# CC110L_Breakout.net
KiCad netlist of a schematic drawn in EAGLE
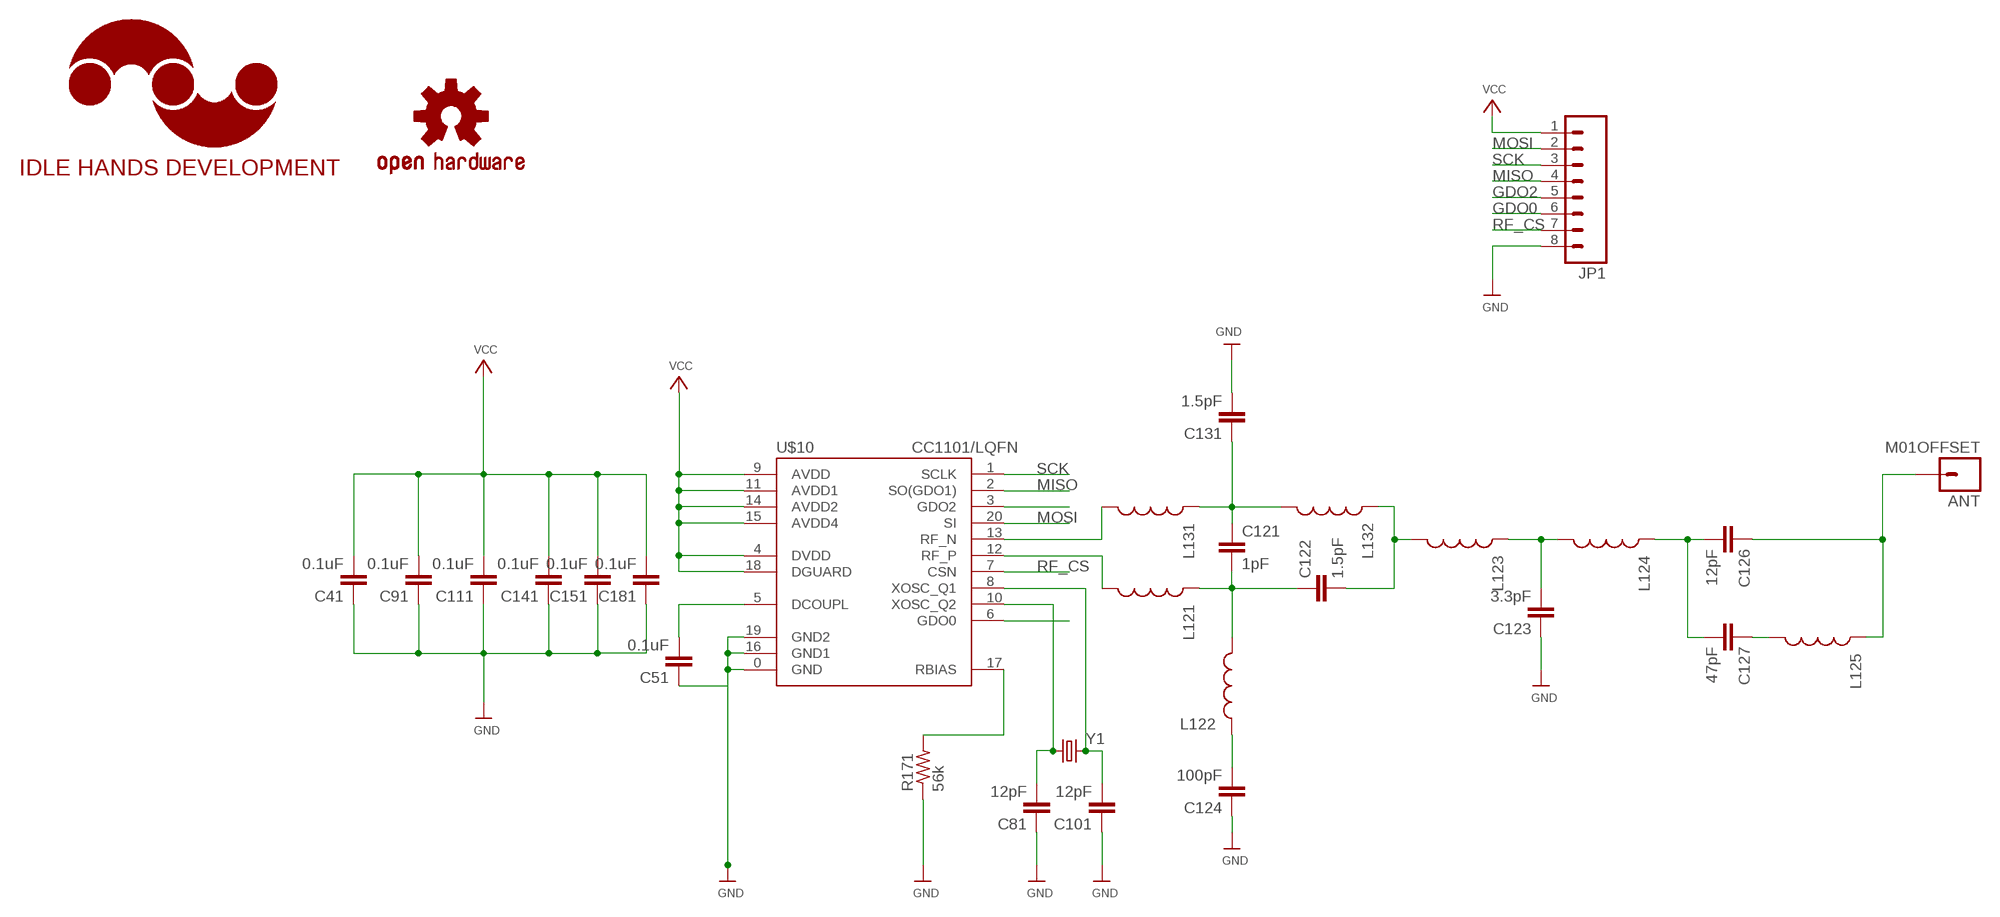
[diagram p0: schematic, sheet 1]

(export (version "E")
  (design (tool "Eeschema 10.0.6"))
  (components
    (comp (ref "ANT")
      (value "M01OFFSET")
      (footprint "eagle-import:1X01_OFFSET")
      (libsource (lib "eagle-import") (part "M01OFFSET"))
    )
    (comp (ref "C41")
      (value "0.1uF")
      (footprint "eagle-import:C0402")
      (libsource (lib "eagle-import") (part "C-EUC0402"))
    )
    (comp (ref "C51")
      (value "0.1uF")
      (footprint "eagle-import:C0402")
      (libsource (lib "eagle-import") (part "C-EUC0402"))
    )
    (comp (ref "C81")
      (value "12pF")
      (footprint "eagle-import:C0402")
      (libsource (lib "eagle-import") (part "C-EUC0402"))
    )
    (comp (ref "C91")
      (value "0.1uF")
      (footprint "eagle-import:C0402")
      (libsource (lib "eagle-import") (part "C-EUC0402"))
    )
    (comp (ref "C101")
      (value "12pF")
      (footprint "eagle-import:C0402")
      (libsource (lib "eagle-import") (part "C-EUC0402"))
    )
    (comp (ref "C111")
      (value "0.1uF")
      (footprint "eagle-import:C0402")
      (libsource (lib "eagle-import") (part "C-EUC0402"))
    )
    (comp (ref "C121")
      (value "1pF")
      (footprint "eagle-import:C0402")
      (libsource (lib "eagle-import") (part "C-EUC0402"))
    )
    (comp (ref "C122")
      (value "1.5pF")
      (footprint "eagle-import:C0402")
      (libsource (lib "eagle-import") (part "C-EUC0402"))
    )
    (comp (ref "C123")
      (value "3.3pF")
      (footprint "eagle-import:C0402")
      (libsource (lib "eagle-import") (part "C-EUC0402"))
    )
    (comp (ref "C124")
      (value "100pF")
      (footprint "eagle-import:C0402")
      (libsource (lib "eagle-import") (part "C-EUC0402"))
    )
    (comp (ref "C126")
      (value "12pF")
      (footprint "eagle-import:C0402")
      (libsource (lib "eagle-import") (part "C-EUC0402"))
    )
    (comp (ref "C127")
      (value "47pF")
      (footprint "eagle-import:C0402")
      (libsource (lib "eagle-import") (part "C-EUC0402"))
    )
    (comp (ref "C131")
      (value "1.5pF")
      (footprint "eagle-import:C0402")
      (libsource (lib "eagle-import") (part "C-EUC0402"))
    )
    (comp (ref "C141")
      (value "0.1uF")
      (footprint "eagle-import:C0402")
      (libsource (lib "eagle-import") (part "C-EUC0402"))
    )
    (comp (ref "C151")
      (value "0.1uF")
      (footprint "eagle-import:C0402")
      (libsource (lib "eagle-import") (part "C-EUC0402"))
    )
    (comp (ref "C181")
      (value "0.1uF")
      (footprint "eagle-import:C0402")
      (libsource (lib "eagle-import") (part "C-EUC0402"))
    )
    (comp (ref "JP1")
      (value "M08LOCK")
      (footprint "eagle-import:1X08_LOCK")
      (libsource (lib "eagle-import") (part "M08LOCK"))
    )
    (comp (ref "L121")
      (value "INDUCTOR0402")
      (footprint "eagle-import:C0402")
      (libsource (lib "eagle-import") (part "INDUCTOR0402"))
    )
    (comp (ref "L122")
      (value "INDUCTOR0402")
      (footprint "eagle-import:C0402")
      (libsource (lib "eagle-import") (part "INDUCTOR0402"))
    )
    (comp (ref "L123")
      (value "INDUCTOR0402")
      (footprint "eagle-import:C0402")
      (libsource (lib "eagle-import") (part "INDUCTOR0402"))
    )
    (comp (ref "L124")
      (value "INDUCTOR0402")
      (footprint "eagle-import:C0402")
      (libsource (lib "eagle-import") (part "INDUCTOR0402"))
    )
    (comp (ref "L125")
      (value "INDUCTOR0402")
      (footprint "eagle-import:C0402")
      (libsource (lib "eagle-import") (part "INDUCTOR0402"))
    )
    (comp (ref "L131")
      (value "INDUCTOR0402")
      (footprint "eagle-import:C0402")
      (libsource (lib "eagle-import") (part "INDUCTOR0402"))
    )
    (comp (ref "L132")
      (value "INDUCTOR0402")
      (footprint "eagle-import:C0402")
      (libsource (lib "eagle-import") (part "INDUCTOR0402"))
    )
    (comp (ref "LOGO1")
      (value "OSHW-LOGOS")
      (footprint "eagle-import:OSHW-LOGO-S")
      (libsource (lib "eagle-import") (part "OSHW-LOGOS"))
    )
    (comp (ref "LOGO2")
      (value "IDLEHANDS_LOGOS")
      (footprint "eagle-import:IHD-LOGO-S")
      (libsource (lib "eagle-import") (part "IDLEHANDS_LOGOS"))
    )
    (comp (ref "R171")
      (value "56k")
      (footprint "eagle-import:R0402")
      (libsource (lib "eagle-import") (part "R-US_R0402"))
    )
    (comp (ref "U$10")
      (value "CC1101/LQFN")
      (footprint "eagle-import:QFN20")
      (libsource (lib "eagle-import") (part "CC1101/LQFN"))
    )
    (comp (ref "Y1")
      (value "CRYSTAL3.2X2.5")
      (footprint "eagle-import:CRYSTAL-SMD-3.2X2.5")
      (libsource (lib "eagle-import") (part "CRYSTAL3.2X2.5"))
    )
  )
  (nets
    (net (code "1") (name "/GDO0") (class "Default")
      (node (ref "JP1") (pin "6") (pinfunction "6_6") (pintype "passive"))
      (node (ref "U$10") (pin "6") (pinfunction "GDO0_6") (pintype "bidirectional"))
    )
    (net (code "2") (name "/GDO2") (class "Default")
      (node (ref "JP1") (pin "5") (pinfunction "5_5") (pintype "passive"))
      (node (ref "U$10") (pin "3") (pinfunction "GDO2_3") (pintype "bidirectional"))
    )
    (net (code "3") (name "/MISO") (class "Default")
      (node (ref "JP1") (pin "4") (pinfunction "4_4") (pintype "passive"))
      (node (ref "U$10") (pin "2") (pinfunction "SO(GDO1)_2") (pintype "bidirectional"))
    )
    (net (code "4") (name "/MOSI") (class "Default")
      (node (ref "JP1") (pin "2") (pinfunction "2_2") (pintype "passive"))
      (node (ref "U$10") (pin "20") (pinfunction "SI_20") (pintype "bidirectional"))
    )
    (net (code "5") (name "/RF_CS") (class "Default")
      (node (ref "JP1") (pin "7") (pinfunction "7_7") (pintype "passive"))
      (node (ref "U$10") (pin "7") (pinfunction "CSN_7") (pintype "bidirectional"))
    )
    (net (code "6") (name "/SCK") (class "Default")
      (node (ref "JP1") (pin "3") (pinfunction "3_3") (pintype "passive"))
      (node (ref "U$10") (pin "1") (pinfunction "SCLK_1") (pintype "bidirectional"))
    )
    (net (code "7") (name "GND") (class "Default")
      (node (ref "C101") (pin "1") (pinfunction "1_1") (pintype "passive"))
      (node (ref "C111") (pin "1") (pinfunction "1_1") (pintype "passive"))
      (node (ref "C123") (pin "1") (pinfunction "1_1") (pintype "passive"))
      (node (ref "C124") (pin "1") (pinfunction "1_1") (pintype "passive"))
      (node (ref "C131") (pin "2") (pinfunction "2_2") (pintype "passive"))
      (node (ref "C141") (pin "1") (pinfunction "1_1") (pintype "passive"))
      (node (ref "C151") (pin "1") (pinfunction "1_1") (pintype "passive"))
      (node (ref "C181") (pin "1") (pinfunction "1_1") (pintype "passive"))
      (node (ref "C41") (pin "1") (pinfunction "1_1") (pintype "passive"))
      (node (ref "C51") (pin "1") (pinfunction "1_1") (pintype "passive"))
      (node (ref "C81") (pin "1") (pinfunction "1_1") (pintype "passive"))
      (node (ref "C91") (pin "1") (pinfunction "1_1") (pintype "passive"))
      (node (ref "JP1") (pin "8") (pinfunction "8_8") (pintype "passive"))
      (node (ref "R171") (pin "1") (pinfunction "1_1") (pintype "passive"))
      (node (ref "U$10") (pin "0") (pinfunction "GND_0") (pintype "bidirectional"))
      (node (ref "U$10") (pin "16") (pinfunction "GND1_16") (pintype "bidirectional"))
      (node (ref "U$10") (pin "19") (pinfunction "GND2_19") (pintype "bidirectional"))
    )
    (net (code "8") (name "Net-(ANT-Pad1)") (class "Default")
      (node (ref "ANT") (pin "1") (pinfunction "1_1") (pintype "passive"))
      (node (ref "C126") (pin "1") (pinfunction "1_1") (pintype "passive"))
      (node (ref "L125") (pin "1") (pinfunction "1_1") (pintype "passive"))
    )
    (net (code "9") (name "Net-(C121-Pad1)") (class "Default")
      (node (ref "C121") (pin "1") (pinfunction "1_1") (pintype "passive"))
      (node (ref "C131") (pin "1") (pinfunction "1_1") (pintype "passive"))
      (node (ref "L131") (pin "1") (pinfunction "1_1") (pintype "passive"))
      (node (ref "L132") (pin "2") (pinfunction "2_2") (pintype "passive"))
    )
    (net (code "10") (name "Net-(C121-Pad2)") (class "Default")
      (node (ref "C121") (pin "2") (pinfunction "2_2") (pintype "passive"))
      (node (ref "C122") (pin "1") (pinfunction "1_1") (pintype "passive"))
      (node (ref "L121") (pin "1") (pinfunction "1_1") (pintype "passive"))
      (node (ref "L122") (pin "2") (pinfunction "2_2") (pintype "passive"))
    )
    (net (code "11") (name "Net-(C122-Pad2)") (class "Default")
      (node (ref "C122") (pin "2") (pinfunction "2_2") (pintype "passive"))
      (node (ref "L123") (pin "2") (pinfunction "2_2") (pintype "passive"))
      (node (ref "L132") (pin "1") (pinfunction "1_1") (pintype "passive"))
    )
    (net (code "12") (name "Net-(C123-Pad2)") (class "Default")
      (node (ref "C123") (pin "2") (pinfunction "2_2") (pintype "passive"))
      (node (ref "L123") (pin "1") (pinfunction "1_1") (pintype "passive"))
      (node (ref "L124") (pin "2") (pinfunction "2_2") (pintype "passive"))
    )
    (net (code "13") (name "Net-(C124-Pad2)") (class "Default")
      (node (ref "C124") (pin "2") (pinfunction "2_2") (pintype "passive"))
      (node (ref "L122") (pin "1") (pinfunction "1_1") (pintype "passive"))
    )
    (net (code "14") (name "Net-(C126-Pad2)") (class "Default")
      (node (ref "C126") (pin "2") (pinfunction "2_2") (pintype "passive"))
      (node (ref "C127") (pin "2") (pinfunction "2_2") (pintype "passive"))
      (node (ref "L124") (pin "1") (pinfunction "1_1") (pintype "passive"))
    )
    (net (code "15") (name "Net-(C127-Pad1)") (class "Default")
      (node (ref "C127") (pin "1") (pinfunction "1_1") (pintype "passive"))
      (node (ref "L125") (pin "2") (pinfunction "2_2") (pintype "passive"))
    )
    (net (code "16") (name "Net-(U$10-DCOUPL)") (class "Default")
      (node (ref "C51") (pin "2") (pinfunction "2_2") (pintype "passive"))
      (node (ref "U$10") (pin "5") (pinfunction "DCOUPL_5") (pintype "bidirectional"))
    )
    (net (code "17") (name "Net-(U$10-RBIAS)") (class "Default")
      (node (ref "R171") (pin "2") (pinfunction "2_2") (pintype "passive"))
      (node (ref "U$10") (pin "17") (pinfunction "RBIAS_17") (pintype "bidirectional"))
    )
    (net (code "18") (name "Net-(U$10-RF_N)") (class "Default")
      (node (ref "L131") (pin "2") (pinfunction "2_2") (pintype "passive"))
      (node (ref "U$10") (pin "13") (pinfunction "RF_N_13") (pintype "bidirectional"))
    )
    (net (code "19") (name "Net-(U$10-RF_P)") (class "Default")
      (node (ref "L121") (pin "2") (pinfunction "2_2") (pintype "passive"))
      (node (ref "U$10") (pin "12") (pinfunction "RF_P_12") (pintype "bidirectional"))
    )
    (net (code "20") (name "Net-(U$10-XOSC_Q1)") (class "Default")
      (node (ref "C101") (pin "2") (pinfunction "2_2") (pintype "passive"))
      (node (ref "U$10") (pin "8") (pinfunction "XOSC_Q1_8") (pintype "bidirectional"))
      (node (ref "Y1") (pin "3") (pinfunction "2_3") (pintype "passive"))
    )
    (net (code "21") (name "Net-(U$10-XOSC_Q2)") (class "Default")
      (node (ref "C81") (pin "2") (pinfunction "2_2") (pintype "passive"))
      (node (ref "U$10") (pin "10") (pinfunction "XOSC_Q2_10") (pintype "bidirectional"))
      (node (ref "Y1") (pin "1") (pinfunction "1_1") (pintype "passive"))
    )
    (net (code "22") (name "VCC") (class "Default")
      (node (ref "C111") (pin "2") (pinfunction "2_2") (pintype "passive"))
      (node (ref "C141") (pin "2") (pinfunction "2_2") (pintype "passive"))
      (node (ref "C151") (pin "2") (pinfunction "2_2") (pintype "passive"))
      (node (ref "C181") (pin "2") (pinfunction "2_2") (pintype "passive"))
      (node (ref "C41") (pin "2") (pinfunction "2_2") (pintype "passive"))
      (node (ref "C91") (pin "2") (pinfunction "2_2") (pintype "passive"))
      (node (ref "JP1") (pin "1") (pinfunction "1_1") (pintype "passive"))
      (node (ref "U$10") (pin "11") (pinfunction "AVDD1_11") (pintype "bidirectional"))
      (node (ref "U$10") (pin "14") (pinfunction "AVDD2_14") (pintype "bidirectional"))
      (node (ref "U$10") (pin "15") (pinfunction "AVDD4_15") (pintype "bidirectional"))
      (node (ref "U$10") (pin "18") (pinfunction "DGUARD_18") (pintype "bidirectional"))
      (node (ref "U$10") (pin "4") (pinfunction "DVDD_4") (pintype "bidirectional"))
      (node (ref "U$10") (pin "9") (pinfunction "AVDD_9") (pintype "bidirectional"))
    )
  )
)
